# Quad_2x1_mux.net
KiCad netlist of a schematic drawn in Altium Designer
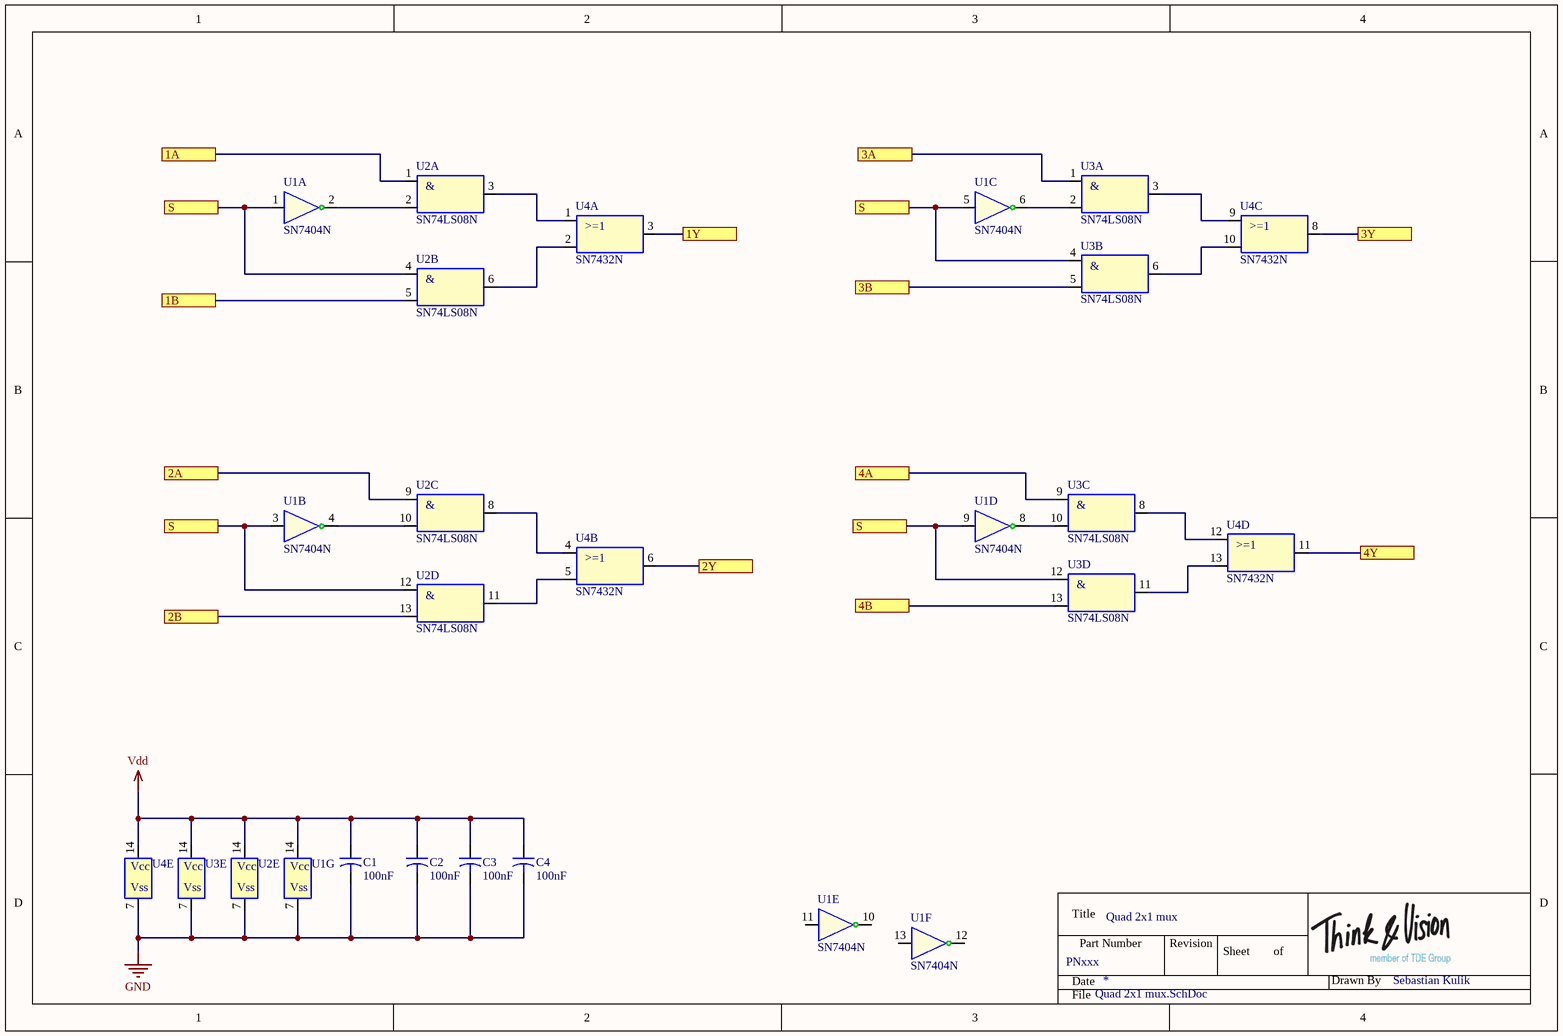
[diagram p0: Quad 2x1 mux.SchDoc]

(export (version "E")
  (design (tool "Eeschema 10.0.6"))
  (components
    (comp (ref "C1")
      (value "100nF")
      (footprint "Dummy-10mm")
      (description "Capacitor-Dummy-THT")
      (fields (field (name "PUBLISHER") "Sebastian Kulik"))
      (libsource (lib "Capacitors") (part "Capacitor-Dummy-THT"))
    )
    (comp (ref "C2")
      (value "100nF")
      (footprint "Dummy-10mm")
      (description "Capacitor-Dummy-THT")
      (fields (field (name "PUBLISHER") "Sebastian Kulik"))
      (libsource (lib "Capacitors") (part "Capacitor-Dummy-THT"))
    )
    (comp (ref "C3")
      (value "100nF")
      (footprint "Dummy-10mm")
      (description "Capacitor-Dummy-THT")
      (fields (field (name "PUBLISHER") "Sebastian Kulik"))
      (libsource (lib "Capacitors") (part "Capacitor-Dummy-THT"))
    )
    (comp (ref "C4")
      (value "100nF")
      (footprint "Dummy-10mm")
      (description "Capacitor-Dummy-THT")
      (fields (field (name "PUBLISHER") "Sebastian Kulik"))
      (libsource (lib "Capacitors") (part "Capacitor-Dummy-THT"))
    )
    (comp (ref "U1")
      (value "SN7404N")
      (footprint "DIP-14")
      (description "Hex Inverter TTL")
      (fields (field (name "MANUFACTURER") "TI") (field (name "PUBLISHER") "Sebastian Kulik"))
      (libsource (lib "ICs") (part "SN7404N"))
    )
    (comp (ref "U2")
      (value "SN74LS08N")
      (footprint "DIP-14")
      (description "Quad AND, TTL")
      (fields (field (name "MANUFACTURER") "TI") (field (name "PUBLISHER") "Sebastian Kulik"))
      (libsource (lib "ICs") (part "SN74LS08N"))
    )
    (comp (ref "U3")
      (value "SN74LS08N")
      (footprint "DIP-14")
      (description "Quad AND, TTL")
      (fields (field (name "MANUFACTURER") "TI") (field (name "PUBLISHER") "Sebastian Kulik"))
      (libsource (lib "ICs") (part "SN74LS08N"))
    )
    (comp (ref "U4")
      (value "SN7432N")
      (footprint "DIP-14")
      (description "Quad NAND, TTL")
      (fields (field (name "MANUFACTURER") "TI") (field (name "PUBLISHER") "Sebastian Kulik"))
      (libsource (lib "ICs") (part "SN7432N"))
    )
  )
  (nets
    (net (code "1") (name "/1A") (class "Default")
      (node (ref "U2") (pin "1") (pinfunction "1A_1") (pintype "passive"))
    )
    (net (code "2") (name "/1B") (class "Default")
      (node (ref "U2") (pin "5") (pinfunction "2B_5") (pintype "passive"))
    )
    (net (code "3") (name "/1Y") (class "Default")
      (node (ref "U4") (pin "3") (pinfunction "Y1_3") (pintype "passive"))
    )
    (net (code "4") (name "/2A") (class "Default")
      (node (ref "U2") (pin "9") (pinfunction "3A_9") (pintype "passive"))
    )
    (net (code "5") (name "/2B") (class "Default")
      (node (ref "U2") (pin "13") (pinfunction "4B_13") (pintype "passive"))
    )
    (net (code "6") (name "/2Y") (class "Default")
      (node (ref "U4") (pin "6") (pinfunction "Y2_6") (pintype "passive"))
    )
    (net (code "7") (name "/3A") (class "Default")
      (node (ref "U3") (pin "1") (pinfunction "1A_1") (pintype "passive"))
    )
    (net (code "8") (name "/3B") (class "Default")
      (node (ref "U3") (pin "5") (pinfunction "2B_5") (pintype "passive"))
    )
    (net (code "9") (name "/3Y") (class "Default")
      (node (ref "U4") (pin "8") (pinfunction "Y3_8") (pintype "passive"))
    )
    (net (code "10") (name "/4A") (class "Default")
      (node (ref "U3") (pin "9") (pinfunction "3A_9") (pintype "passive"))
    )
    (net (code "11") (name "/4B") (class "Default")
      (node (ref "U3") (pin "13") (pinfunction "4B_13") (pintype "passive"))
    )
    (net (code "12") (name "/4Y") (class "Default")
      (node (ref "U4") (pin "11") (pinfunction "Y4_11") (pintype "passive"))
    )
    (net (code "13") (name "/S") (class "Default")
      (node (ref "U1") (pin "1") (pinfunction "1A_1") (pintype "passive"))
      (node (ref "U1") (pin "3") (pinfunction "2A_3") (pintype "passive"))
      (node (ref "U1") (pin "5") (pinfunction "3A_5") (pintype "passive"))
      (node (ref "U1") (pin "9") (pinfunction "4A_9") (pintype "passive"))
      (node (ref "U2") (pin "12") (pinfunction "4A_12") (pintype "passive"))
      (node (ref "U2") (pin "4") (pinfunction "2A_4") (pintype "passive"))
      (node (ref "U3") (pin "12") (pinfunction "4A_12") (pintype "passive"))
      (node (ref "U3") (pin "4") (pinfunction "2A_4") (pintype "passive"))
    )
    (net (code "14") (name "GND") (class "Default")
      (node (ref "C1") (pin "2") (pinfunction "2_2") (pintype "passive"))
      (node (ref "C2") (pin "2") (pinfunction "2_2") (pintype "passive"))
      (node (ref "C3") (pin "2") (pinfunction "2_2") (pintype "passive"))
      (node (ref "C4") (pin "2") (pinfunction "2_2") (pintype "passive"))
      (node (ref "U1") (pin "7") (pinfunction "Vss_7") (pintype "passive"))
      (node (ref "U2") (pin "7") (pinfunction "Vss_7") (pintype "passive"))
      (node (ref "U3") (pin "7") (pinfunction "Vss_7") (pintype "passive"))
      (node (ref "U4") (pin "7") (pinfunction "Vss_7") (pintype "passive"))
    )
    (net (code "15") (name "Net-(U1A-1Y)") (class "Default")
      (node (ref "U1") (pin "2") (pinfunction "1Y_2") (pintype "passive"))
      (node (ref "U2") (pin "2") (pinfunction "1B_2") (pintype "passive"))
    )
    (net (code "16") (name "Net-(U1B-2Y)") (class "Default")
      (node (ref "U1") (pin "4") (pinfunction "2Y_4") (pintype "passive"))
      (node (ref "U2") (pin "10") (pinfunction "3B_10") (pintype "passive"))
    )
    (net (code "17") (name "Net-(U1C-3Y)") (class "Default")
      (node (ref "U1") (pin "6") (pinfunction "3Y_6") (pintype "passive"))
      (node (ref "U3") (pin "2") (pinfunction "1B_2") (pintype "passive"))
    )
    (net (code "18") (name "Net-(U1D-Y4)") (class "Default")
      (node (ref "U1") (pin "8") (pinfunction "Y4_8") (pintype "passive"))
      (node (ref "U3") (pin "10") (pinfunction "3B_10") (pintype "passive"))
    )
    (net (code "19") (name "Net-(U2A-Y1)") (class "Default")
      (node (ref "U2") (pin "3") (pinfunction "Y1_3") (pintype "passive"))
      (node (ref "U4") (pin "1") (pinfunction "1A_1") (pintype "passive"))
    )
    (net (code "20") (name "Net-(U2B-Y2)") (class "Default")
      (node (ref "U2") (pin "6") (pinfunction "Y2_6") (pintype "passive"))
      (node (ref "U4") (pin "2") (pinfunction "1B_2") (pintype "passive"))
    )
    (net (code "21") (name "Net-(U2C-Y3)") (class "Default")
      (node (ref "U2") (pin "8") (pinfunction "Y3_8") (pintype "passive"))
      (node (ref "U4") (pin "4") (pinfunction "2A_4") (pintype "passive"))
    )
    (net (code "22") (name "Net-(U2D-Y4)") (class "Default")
      (node (ref "U2") (pin "11") (pinfunction "Y4_11") (pintype "passive"))
      (node (ref "U4") (pin "5") (pinfunction "2B_5") (pintype "passive"))
    )
    (net (code "23") (name "Net-(U3A-Y1)") (class "Default")
      (node (ref "U3") (pin "3") (pinfunction "Y1_3") (pintype "passive"))
      (node (ref "U4") (pin "9") (pinfunction "3A_9") (pintype "passive"))
    )
    (net (code "24") (name "Net-(U3B-Y2)") (class "Default")
      (node (ref "U3") (pin "6") (pinfunction "Y2_6") (pintype "passive"))
      (node (ref "U4") (pin "10") (pinfunction "3B_10") (pintype "passive"))
    )
    (net (code "25") (name "Net-(U3C-Y3)") (class "Default")
      (node (ref "U3") (pin "8") (pinfunction "Y3_8") (pintype "passive"))
      (node (ref "U4") (pin "12") (pinfunction "4A_12") (pintype "passive"))
    )
    (net (code "26") (name "Net-(U3D-Y4)") (class "Default")
      (node (ref "U3") (pin "11") (pinfunction "Y4_11") (pintype "passive"))
      (node (ref "U4") (pin "13") (pinfunction "4B_13") (pintype "passive"))
    )
    (net (code "27") (name "Vdd") (class "Default")
      (node (ref "C1") (pin "1") (pinfunction "1_1") (pintype "passive"))
      (node (ref "C2") (pin "1") (pinfunction "1_1") (pintype "passive"))
      (node (ref "C3") (pin "1") (pinfunction "1_1") (pintype "passive"))
      (node (ref "C4") (pin "1") (pinfunction "1_1") (pintype "passive"))
      (node (ref "U1") (pin "14") (pinfunction "Vcc_14") (pintype "passive"))
      (node (ref "U2") (pin "14") (pinfunction "Vcc_14") (pintype "passive"))
      (node (ref "U3") (pin "14") (pinfunction "Vcc_14") (pintype "passive"))
      (node (ref "U4") (pin "14") (pinfunction "Vcc_14") (pintype "passive"))
    )
    (net (code "28") (name "unconnected-(U1E-5A-Pad11)") (class "Default")
      (node (ref "U1") (pin "11") (pinfunction "5A_11") (pintype "passive"))
    )
    (net (code "29") (name "unconnected-(U1E-5Y-Pad10)") (class "Default")
      (node (ref "U1") (pin "10") (pinfunction "5Y_10") (pintype "passive"))
    )
    (net (code "30") (name "unconnected-(U1F-6A-Pad13)") (class "Default")
      (node (ref "U1") (pin "13") (pinfunction "6A_13") (pintype "passive"))
    )
    (net (code "31") (name "unconnected-(U1F-6Y-Pad12)") (class "Default")
      (node (ref "U1") (pin "12") (pinfunction "6Y_12") (pintype "passive"))
    )
  )
)
